# Input.net
KiCad netlist of a schematic drawn in Altium Designer
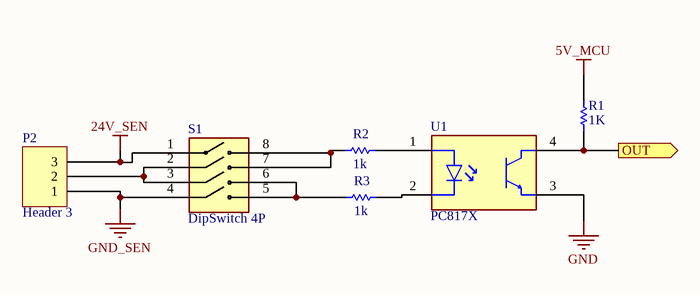
[diagram p0: Input.SchDoc]

(export (version "E")
  (design (tool "Eeschema 10.0.6"))
  (components
    (comp (ref "P2")
      (value "Header 3")
      (footprint "HDR1X3")
      (description "Header, 3-Pin")
      (fields (field (name "PUBLISHER") "Altium Limited"))
      (libsource (lib "Miscellaneous Connectors") (part "Header 3"))
    )
    (comp (ref "R1")
      (value "1K")
      (footprint "SMT0805_M")
      (description "Resistor")
      (fields (field (name "Comment") "0805/.125W/5Q") (field (name "PUBLISHER") "Altium Limited"))
      (libsource (lib "Miscellaneous Devices") (part "Res1"))
    )
    (comp (ref "R2")
      (value "1k")
      (footprint "SMT0805_M")
      (description "Resistor")
      (fields (field (name "Comment") "0805/.125W/5Q") (field (name "PUBLISHER") "Altium Limited"))
      (libsource (lib "Miscellaneous Devices") (part "Res1"))
    )
    (comp (ref "R3")
      (value "1k")
      (footprint "SMT0805_M")
      (description "Resistor")
      (fields (field (name "Comment") "0805/.125W/5Q") (field (name "PUBLISHER") "Altium Limited"))
      (libsource (lib "Miscellaneous Devices") (part "Res1"))
    )
    (comp (ref "S1")
      (value "DipSwitch 4P")
      (footprint "DS-04")
      (libsource (lib "ComponentLibrary") (part "DS-04"))
    )
    (comp (ref "U1")
      (value "PC817X")
      (footprint "DIP-4")
      (libsource (lib "ComponentLibrary") (part "PC817X"))
    )
  )
  (nets
    (net (code "1") (name "/OUT") (class "Default")
      (node (ref "R1") (pin "1") (pinfunction "1_1") (pintype "passive"))
      (node (ref "U1") (pin "4") (pinfunction "C_4") (pintype "passive"))
    )
    (net (code "2") (name "5V_MCU") (class "Default")
      (node (ref "R1") (pin "2") (pinfunction "2_2") (pintype "passive"))
    )
    (net (code "3") (name "24V_SEN") (class "Default")
      (node (ref "P2") (pin "3") (pinfunction "3_3") (pintype "passive"))
      (node (ref "S1") (pin "1") (pinfunction "1_1") (pintype "passive"))
    )
    (net (code "4") (name "GND") (class "Default")
      (node (ref "U1") (pin "3") (pinfunction "E_3") (pintype "passive"))
    )
    (net (code "5") (name "GND_SEN") (class "Default")
      (node (ref "P2") (pin "1") (pinfunction "1_1") (pintype "passive"))
      (node (ref "S1") (pin "4") (pinfunction "4_4") (pintype "passive"))
    )
    (net (code "6") (name "Net-(P2-Pad2)") (class "Default")
      (node (ref "P2") (pin "2") (pinfunction "2_2") (pintype "passive"))
      (node (ref "S1") (pin "2") (pinfunction "2_2") (pintype "passive"))
      (node (ref "S1") (pin "3") (pinfunction "3_3") (pintype "passive"))
    )
    (net (code "7") (name "Net-(R2-Pad1)") (class "Default")
      (node (ref "R2") (pin "1") (pinfunction "1_1") (pintype "passive"))
      (node (ref "S1") (pin "7") (pinfunction "7_7") (pintype "passive"))
      (node (ref "S1") (pin "8") (pinfunction "8_8") (pintype "passive"))
    )
    (net (code "8") (name "Net-(R3-Pad1)") (class "Default")
      (node (ref "R3") (pin "1") (pinfunction "1_1") (pintype "passive"))
      (node (ref "S1") (pin "5") (pinfunction "5_5") (pintype "passive"))
      (node (ref "S1") (pin "6") (pinfunction "6_6") (pintype "passive"))
    )
    (net (code "9") (name "Net-(U1-A)") (class "Default")
      (node (ref "R2") (pin "2") (pinfunction "2_2") (pintype "passive"))
      (node (ref "U1") (pin "1") (pinfunction "A_1") (pintype "passive"))
    )
    (net (code "10") (name "Net-(U1-K)") (class "Default")
      (node (ref "R3") (pin "2") (pinfunction "2_2") (pintype "passive"))
      (node (ref "U1") (pin "2") (pinfunction "K_2") (pintype "passive"))
    )
  )
)
